# Hall_Latch.net
KiCad netlist of a schematic drawn in Altium Designer
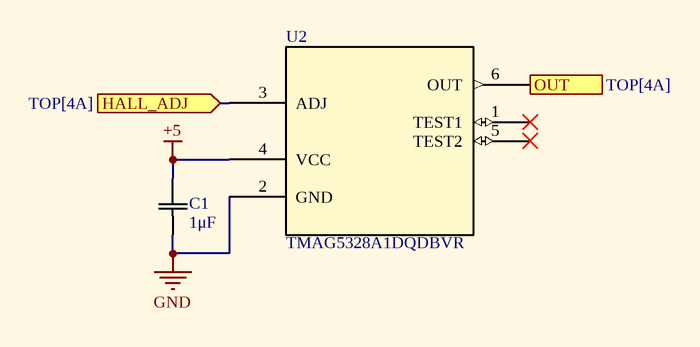
[diagram p0: Hall_Latch.SchDoc]

(export (version "E")
  (design (tool "Eeschema 10.0.6"))
  (components
    (comp (ref "C1")
      (value "1μF")
      (footprint "CAP_CL10_SAM")
      (description "No Description Available")
      (libsource (lib "Component_Schematics") (part "CL10B104KB8NNWC"))
    )
    (comp (ref "U2")
      (value "TMAG5328A1DQDBVR")
      (footprint "SOT23_DBV_TEX")
      (description "No Description Available")
      (fields (field (name "COPYRIGHT") "Copyright (C) 2023 Ultra Librarian. All rights reserved."))
      (libsource (lib "Component_Schematics") (part "TMAG5328A1DQDBVR"))
    )
  )
  (nets
    (net (code "1") (name "+5") (class "Default")
      (node (ref "C1") (pin "2") (pinfunction "2_2") (pintype "passive"))
      (node (ref "U2") (pin "4") (pinfunction "VCC_4") (pintype "power_in"))
    )
    (net (code "2") (name "/HALL_ADJ") (class "Default")
      (node (ref "U2") (pin "3") (pinfunction "ADJ_3") (pintype "passive"))
    )
    (net (code "3") (name "/OUT") (class "Default")
      (node (ref "U2") (pin "6") (pinfunction "OUT_6") (pintype "output"))
    )
    (net (code "4") (name "GND") (class "Default")
      (node (ref "C1") (pin "1") (pinfunction "1_1") (pintype "passive"))
      (node (ref "U2") (pin "2") (pinfunction "GND_2") (pintype "power_in"))
    )
    (net (code "5") (name "unconnected-(U2-TEST1-Pad1)") (class "Default")
      (node (ref "U2") (pin "1") (pinfunction "TEST1_1") (pintype "bidirectional+no_connect"))
    )
    (net (code "6") (name "unconnected-(U2-TEST2-Pad5)") (class "Default")
      (node (ref "U2") (pin "5") (pinfunction "TEST2_5") (pintype "bidirectional+no_connect"))
    )
  )
)
